# TDA2050_Audio_Amplifier.net
KiCad netlist of a schematic drawn in EasyEDA
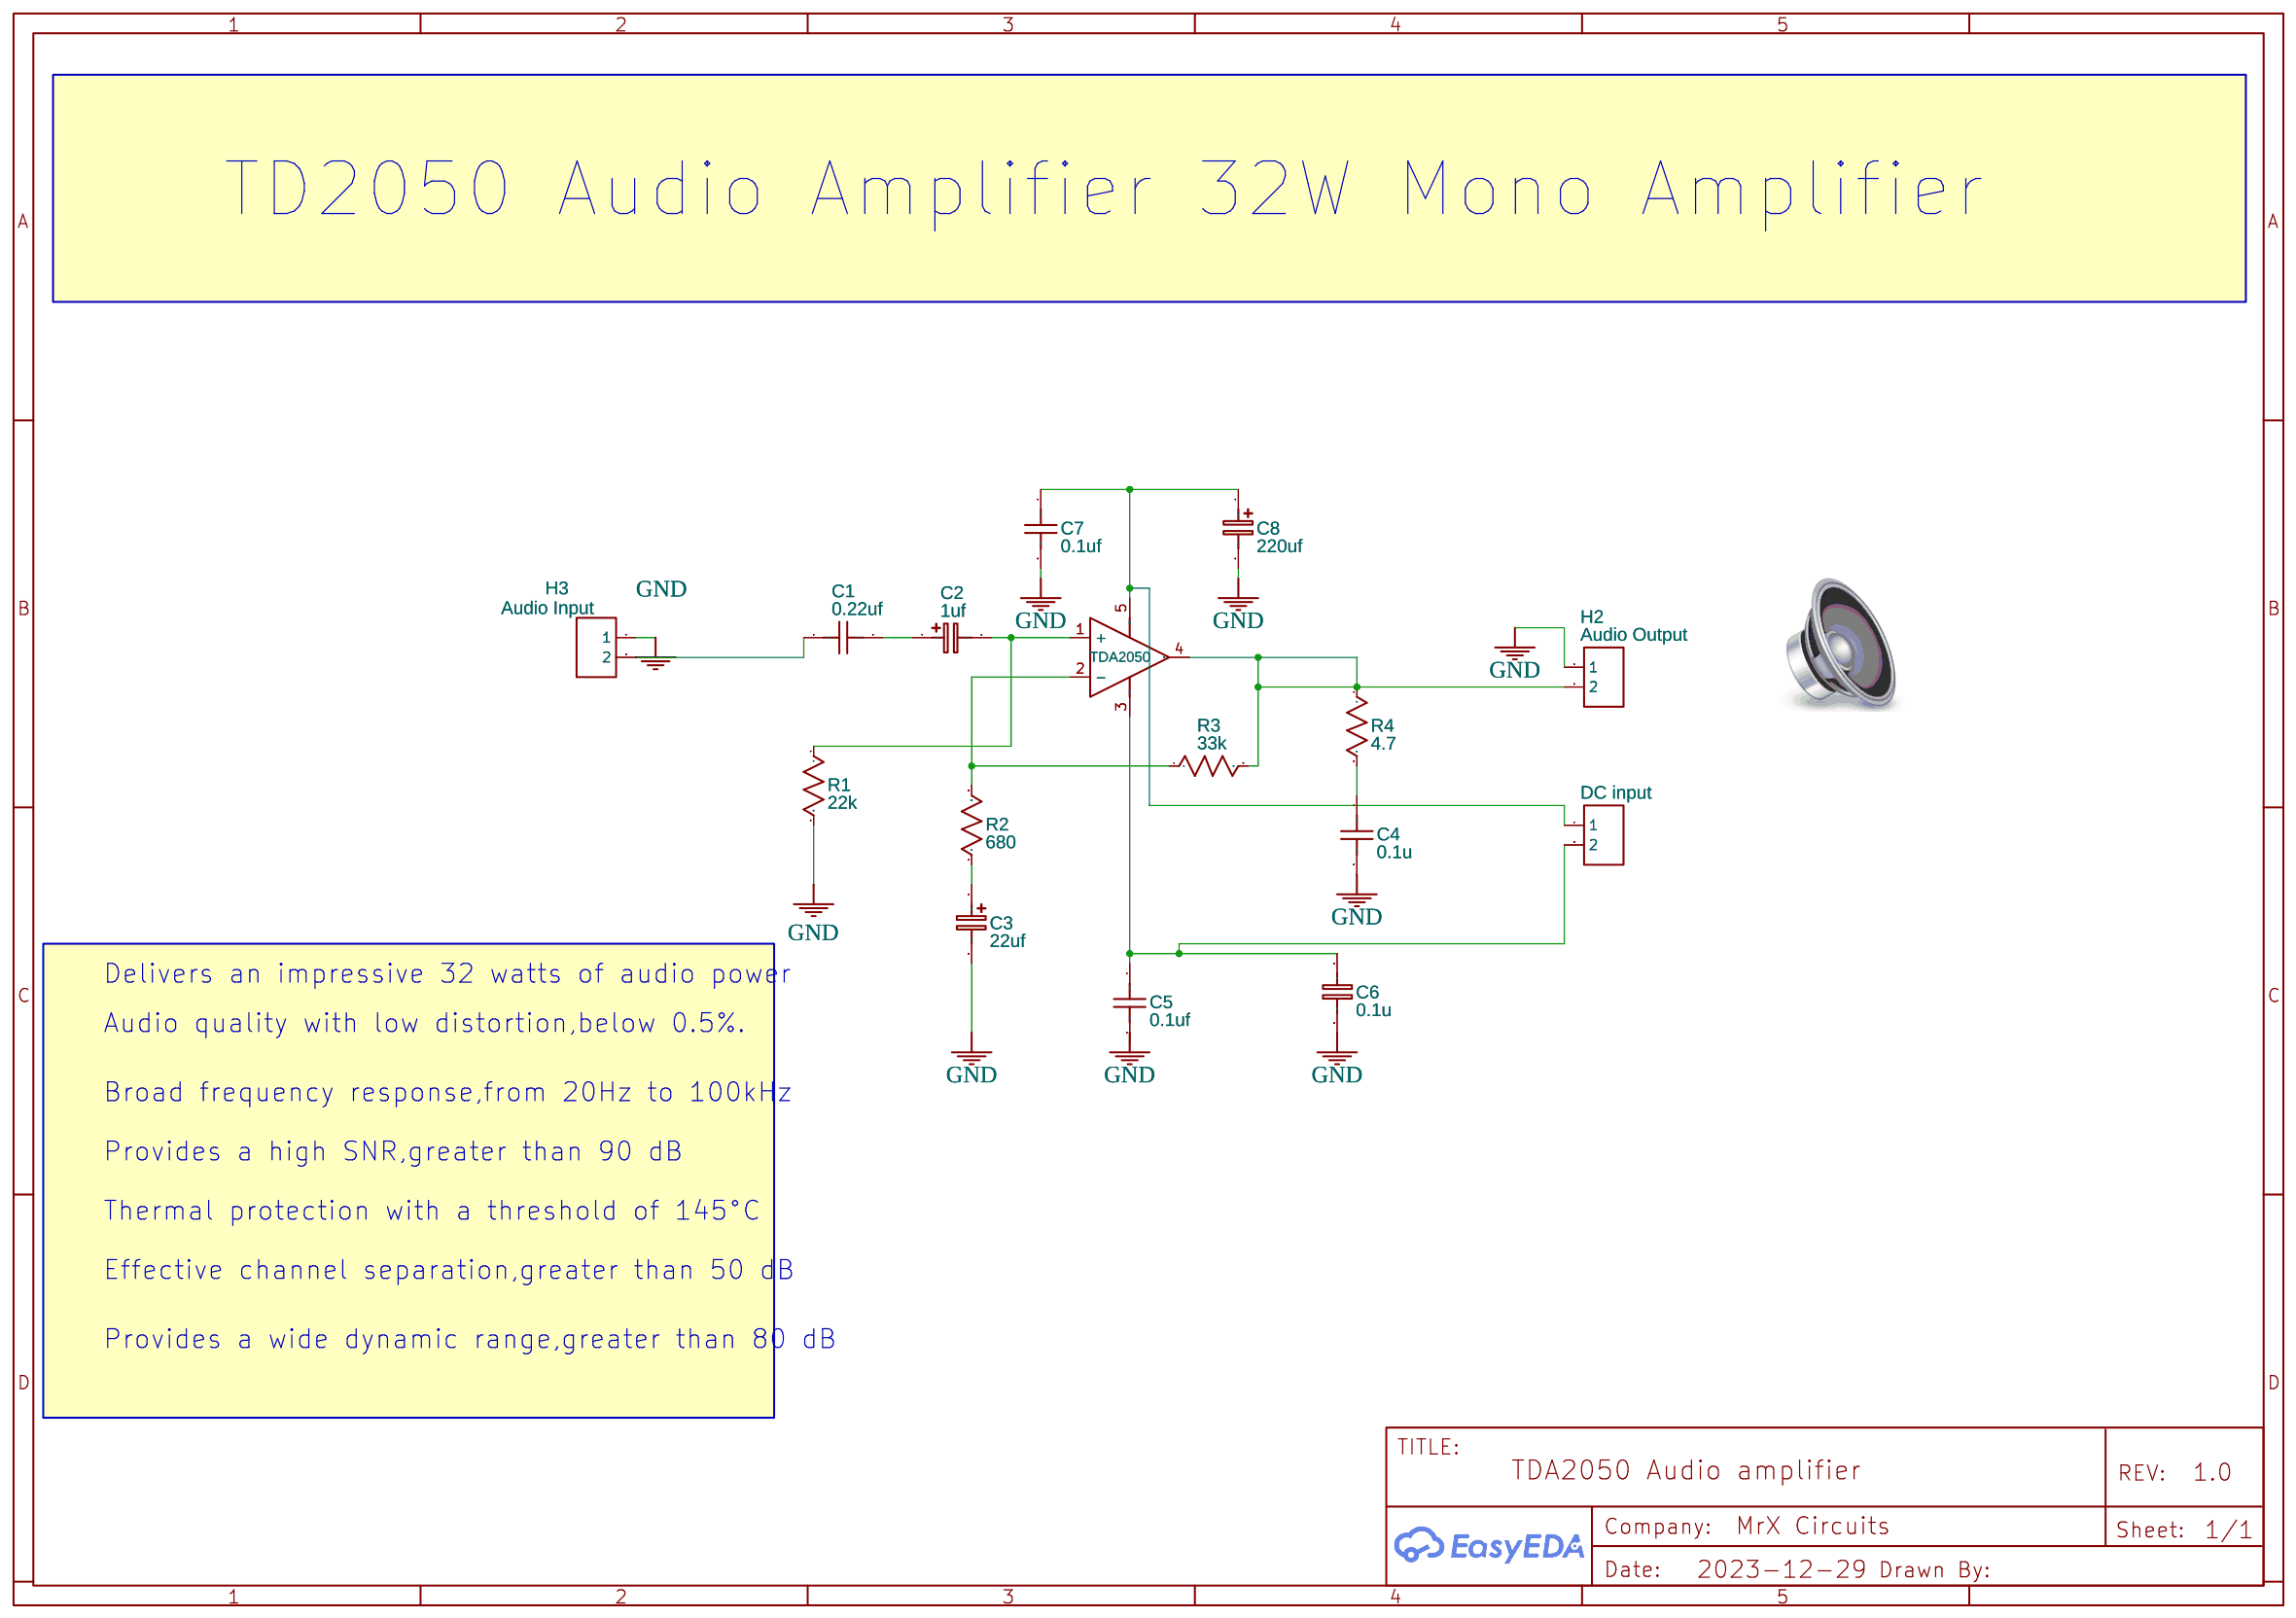
[diagram p0: schematic sheet]

(export (version "E")
  (design (tool "Eeschema 10.0.6"))
  (components
    (comp (ref "C1") (value "0.22uf") (libsource (lib "") (part "C_0603_US")))
    (comp (ref "C2") (value "1uf") (libsource (lib "") (part "C_Tan_SMD_E_EU")))
    (comp (ref "C3") (value "22uf") (libsource (lib "") (part "C_Tan_SMD_E_EU_1")))
    (comp (ref "C4") (value "0.1u") (libsource (lib "") (part "C_0603_US_1")))
    (comp (ref "C5") (value "0.1uf") (libsource (lib "") (part "C_0603_US_1")))
    (comp (ref "C6") (value "0.1u") (libsource (lib "") (part "C_0603_EU")))
    (comp (ref "C7") (value "0.1uf") (libsource (lib "") (part "C_0603_US_1")))
    (comp (ref "C8") (value "220uf") (libsource (lib "") (part "C_Tan_SMD_E_EU_2")))
    (comp (ref "H1") (value "DC input") (libsource (lib "") (part "HDR-F-2.54_1x2_1")))
    (comp (ref "H2") (value "Audio Output") (libsource (lib "") (part "HDR-F-2.54_1x2_1")))
    (comp (ref "H3") (value "Audio Input") (libsource (lib "") (part "HDR-F-2.54_1x2")))
    (comp (ref "R1") (value "22k") (libsource (lib "") (part "R_0603_US")))
    (comp (ref "R2") (value "680") (libsource (lib "") (part "R_0603_US_1")))
    (comp (ref "R3") (value "33k") (libsource (lib "") (part "R_0603_US_2")))
    (comp (ref "R4") (value "4.7") (libsource (lib "") (part "R_0603_US")))
    (comp (ref "U1")
      (value "TDA2050")
      (fields (field (name "Manufacturer Part") "TDA2050L-TB5-T") (field (name "Manufacturer") "UTC(友顺)"))
      (libsource (lib "") (part "TDA2050L-TB5-T"))
    )
  )
  (nets
    (net (code "1") (name "GND") (class "Default")
      (node (ref "C3") (pin "2") (pinfunction "2_2") (pintype "unspecified"))
      (node (ref "C4") (pin "2") (pinfunction "2_2") (pintype "unspecified"))
      (node (ref "C5") (pin "2") (pinfunction "2_2") (pintype "unspecified"))
      (node (ref "C6") (pin "2") (pinfunction "2_2") (pintype "unspecified"))
      (node (ref "C7") (pin "2") (pinfunction "2_2") (pintype "unspecified"))
      (node (ref "C8") (pin "2") (pinfunction "2_2") (pintype "unspecified"))
      (node (ref "H2") (pin "1") (pinfunction "1_1") (pintype "input"))
      (node (ref "H3") (pin "1") (pinfunction "1_1") (pintype "input"))
      (node (ref "R1") (pin "2") (pinfunction "2_2") (pintype "unspecified"))
    )
    (net (code "2") (name "Net-(C1-Pad1)") (class "Default")
      (node (ref "C1") (pin "1") (pinfunction "1_1") (pintype "unspecified"))
      (node (ref "H3") (pin "2") (pinfunction "2_2") (pintype "input"))
    )
    (net (code "3") (name "Net-(C1-Pad2)") (class "Default")
      (node (ref "C1") (pin "2") (pinfunction "2_2") (pintype "unspecified"))
      (node (ref "C2") (pin "1") (pinfunction "1_1") (pintype "unspecified"))
    )
    (net (code "4") (name "Net-(C3-Pad1)") (class "Default")
      (node (ref "C3") (pin "1") (pinfunction "1_1") (pintype "unspecified"))
      (node (ref "R2") (pin "1") (pinfunction "1_1") (pintype "unspecified"))
    )
    (net (code "5") (name "Net-(C4-Pad1)") (class "Default")
      (node (ref "C4") (pin "1") (pinfunction "1_1") (pintype "unspecified"))
      (node (ref "R4") (pin "2") (pinfunction "2_2") (pintype "unspecified"))
    )
    (net (code "6") (name "Net-(U1-+)") (class "Default")
      (node (ref "C2") (pin "2") (pinfunction "2_2") (pintype "unspecified"))
      (node (ref "R1") (pin "1") (pinfunction "1_1") (pintype "unspecified"))
      (node (ref "U1") (pin "1") (pinfunction "+_1") (pintype "unspecified"))
    )
    (net (code "7") (name "Net-(U1--)") (class "Default")
      (node (ref "R2") (pin "2") (pinfunction "2_2") (pintype "unspecified"))
      (node (ref "R3") (pin "1") (pinfunction "1_1") (pintype "unspecified"))
      (node (ref "U1") (pin "2") (pinfunction "-_2") (pintype "unspecified"))
    )
    (net (code "8") (name "Net-(U1-GND)") (class "Default")
      (node (ref "C5") (pin "1") (pinfunction "1_1") (pintype "unspecified"))
      (node (ref "C6") (pin "1") (pinfunction "1_1") (pintype "unspecified"))
      (node (ref "H1") (pin "2") (pinfunction "2_2") (pintype "input"))
      (node (ref "U1") (pin "3") (pinfunction "GND_3") (pintype "unspecified"))
    )
    (net (code "9") (name "Net-(U1-OUT)") (class "Default")
      (node (ref "H2") (pin "2") (pinfunction "2_2") (pintype "input"))
      (node (ref "R3") (pin "2") (pinfunction "2_2") (pintype "unspecified"))
      (node (ref "R4") (pin "1") (pinfunction "1_1") (pintype "unspecified"))
      (node (ref "U1") (pin "4") (pinfunction "OUT_4") (pintype "unspecified"))
    )
    (net (code "10") (name "Net-(U1-VCC+)") (class "Default")
      (node (ref "C7") (pin "1") (pinfunction "1_1") (pintype "unspecified"))
      (node (ref "C8") (pin "1") (pinfunction "1_1") (pintype "unspecified"))
      (node (ref "H1") (pin "1") (pinfunction "1_1") (pintype "input"))
      (node (ref "U1") (pin "5") (pinfunction "VCC+_5") (pintype "unspecified"))
    )
  )
)
